# control_board.net
KiCad netlist of a schematic drawn in EAGLE
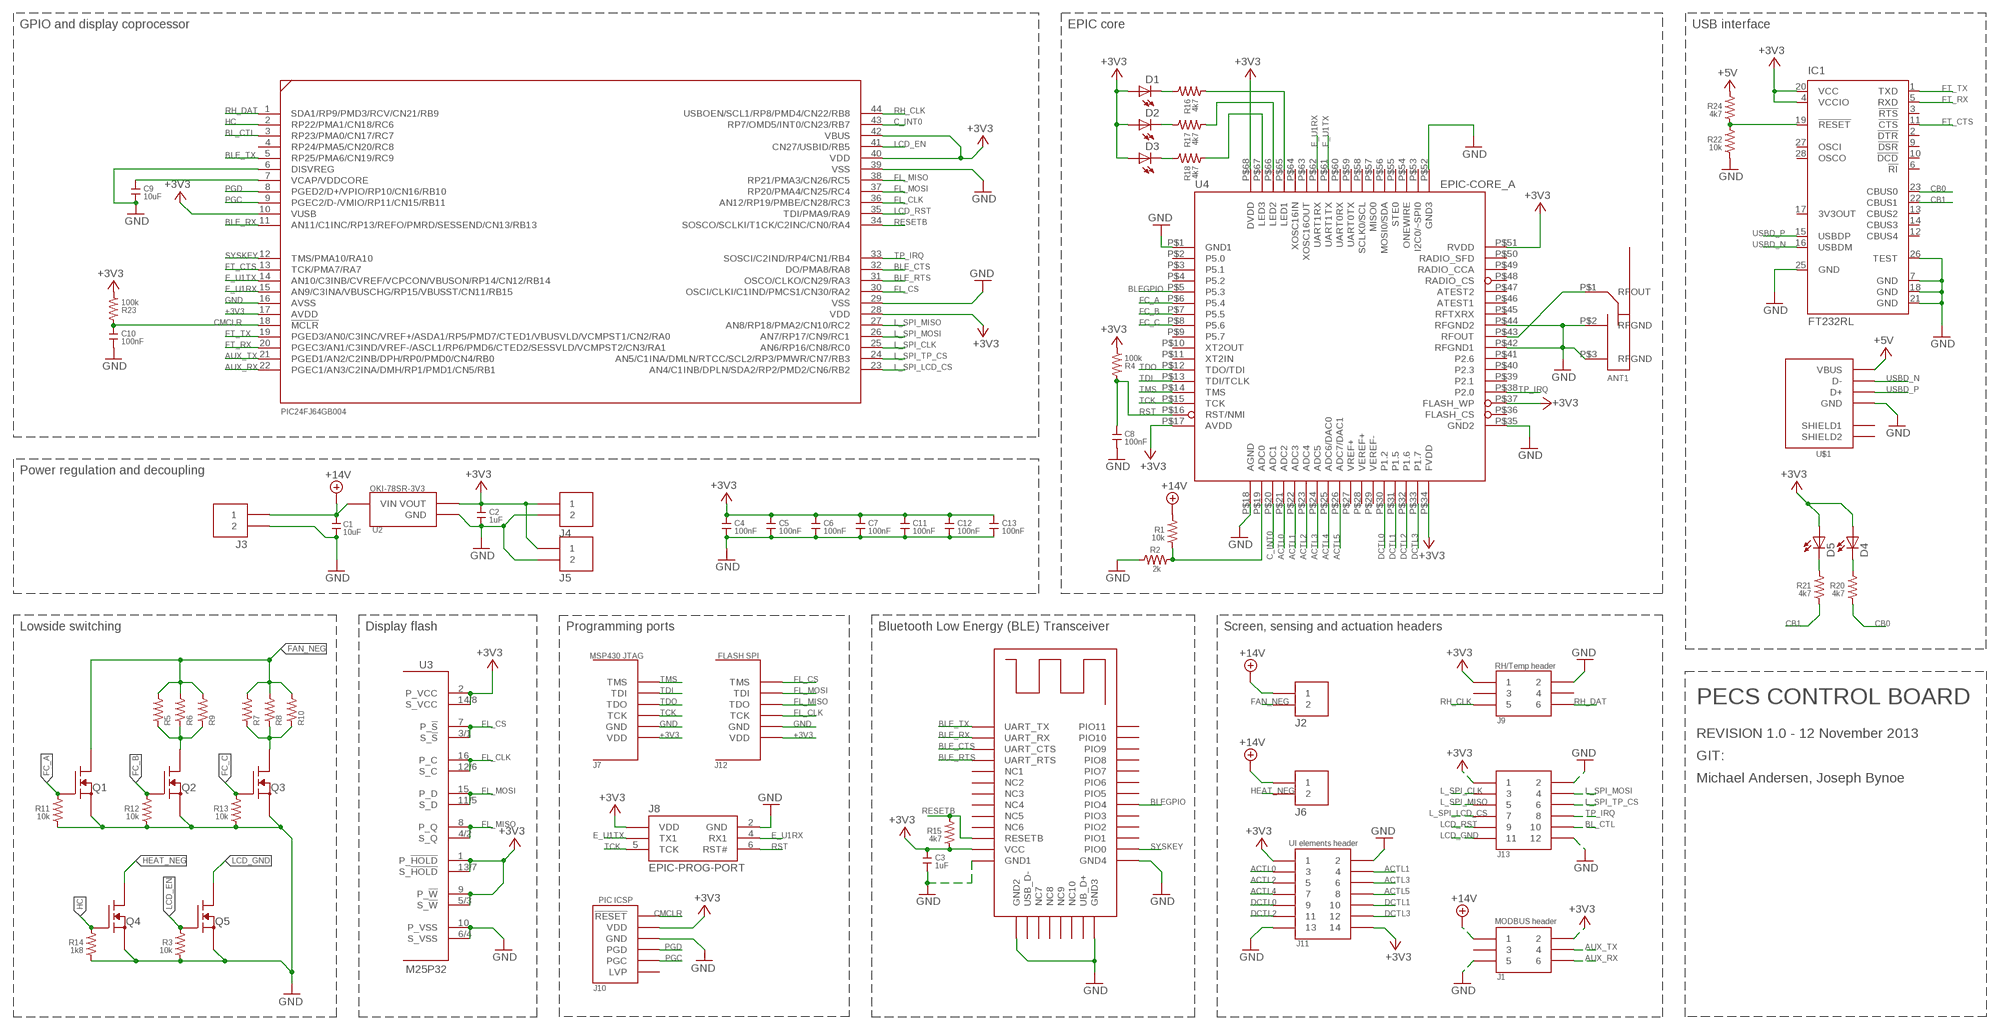
[diagram p0: schematic, sheet 1]

(export (version "E")
  (design (tool "Eeschema 10.0.6"))
  (components
    (comp (ref "ANT1")
      (value "PIFA-2.4GHZ")
      (footprint "eagle-import:PIFA-2.4GHZ")
      (libsource (lib "eagle-import") (part "PIFA-2.4GHZ"))
    )
    (comp (ref "BLE1")
      (value "HM10_BLE")
      (footprint "eagle-import:HM10")
      (libsource (lib "eagle-import") (part "HM10_BLE"))
    )
    (comp (ref "C1")
      (value "10uF")
      (footprint "eagle-import:0805")
      (libsource (lib "eagle-import") (part "0805_CAPACITOR"))
    )
    (comp (ref "C2")
      (value "1uF")
      (footprint "eagle-import:0805")
      (libsource (lib "eagle-import") (part "0805_CAPACITOR"))
    )
    (comp (ref "C3")
      (value "1uF")
      (footprint "eagle-import:0805")
      (libsource (lib "eagle-import") (part "0805_CAPACITOR"))
    )
    (comp (ref "C4")
      (value "100nF")
      (footprint "eagle-import:0805")
      (libsource (lib "eagle-import") (part "0805_CAPACITOR"))
    )
    (comp (ref "C5")
      (value "100nF")
      (footprint "eagle-import:0805")
      (libsource (lib "eagle-import") (part "0805_CAPACITOR"))
    )
    (comp (ref "C6")
      (value "100nF")
      (footprint "eagle-import:0805")
      (libsource (lib "eagle-import") (part "0805_CAPACITOR"))
    )
    (comp (ref "C7")
      (value "100nF")
      (footprint "eagle-import:0805")
      (libsource (lib "eagle-import") (part "0805_CAPACITOR"))
    )
    (comp (ref "C8")
      (value "100nF")
      (footprint "eagle-import:0805")
      (libsource (lib "eagle-import") (part "0805_CAPACITOR"))
    )
    (comp (ref "C9")
      (value "10uF")
      (footprint "eagle-import:0805")
      (libsource (lib "eagle-import") (part "0805_CAPACITOR"))
    )
    (comp (ref "C10")
      (value "100nF")
      (footprint "eagle-import:0805")
      (libsource (lib "eagle-import") (part "0805_CAPACITOR"))
    )
    (comp (ref "C11")
      (value "100nF")
      (footprint "eagle-import:0805")
      (libsource (lib "eagle-import") (part "0805_CAPACITOR"))
    )
    (comp (ref "C12")
      (value "100nF")
      (footprint "eagle-import:0805")
      (libsource (lib "eagle-import") (part "0805_CAPACITOR"))
    )
    (comp (ref "C13")
      (value "100nF")
      (footprint "eagle-import:0805")
      (libsource (lib "eagle-import") (part "0805_CAPACITOR"))
    )
    (comp (ref "D1")
      (value "LED1206")
      (footprint "eagle-import:LED-1206")
      (libsource (lib "eagle-import") (part "LED1206"))
    )
    (comp (ref "D2")
      (value "LED1206")
      (footprint "eagle-import:LED-1206")
      (libsource (lib "eagle-import") (part "LED1206"))
    )
    (comp (ref "D3")
      (value "LED1206")
      (footprint "eagle-import:LED-1206")
      (libsource (lib "eagle-import") (part "LED1206"))
    )
    (comp (ref "D4")
      (value "LED1206")
      (footprint "eagle-import:LED-1206")
      (libsource (lib "eagle-import") (part "LED1206"))
    )
    (comp (ref "D5")
      (value "LED1206")
      (footprint "eagle-import:LED-1206")
      (libsource (lib "eagle-import") (part "LED1206"))
    )
    (comp (ref "IC1")
      (value "FT232RL")
      (footprint "eagle-import:SSOP28")
      (libsource (lib "eagle-import") (part "FT232RL"))
    )
    (comp (ref "J1")
      (value "HD.1-6")
      (footprint "eagle-import:HD.1-6")
      (libsource (lib "eagle-import") (part "HD.1-6"))
    )
    (comp (ref "J2")
      (value "H.1-2")
      (footprint "eagle-import:H.1-2")
      (libsource (lib "eagle-import") (part "H.1-2"))
    )
    (comp (ref "J3")
      (value "H.1-2")
      (footprint "eagle-import:H.1-2")
      (libsource (lib "eagle-import") (part "H.1-2"))
    )
    (comp (ref "J4")
      (value "H.1-2")
      (footprint "eagle-import:H.1-2")
      (libsource (lib "eagle-import") (part "H.1-2"))
    )
    (comp (ref "J5")
      (value "H.1-2")
      (footprint "eagle-import:H.1-2")
      (libsource (lib "eagle-import") (part "H.1-2"))
    )
    (comp (ref "J6")
      (value "H.1-2")
      (footprint "eagle-import:H.1-2")
      (libsource (lib "eagle-import") (part "H.1-2"))
    )
    (comp (ref "J7")
      (value "JTAG")
      (footprint "eagle-import:JTAG")
      (libsource (lib "eagle-import") (part "JTAG"))
    )
    (comp (ref "J8")
      (value "EPIC-PROG-PORT")
      (footprint "eagle-import:HEADER2X3X2MM")
      (libsource (lib "eagle-import") (part "EPIC-PROG-PORT"))
    )
    (comp (ref "J9")
      (value "HD.1-6")
      (footprint "eagle-import:HD.1-6")
      (libsource (lib "eagle-import") (part "HD.1-6"))
    )
    (comp (ref "J10")
      (value "ICSP_HDR")
      (footprint "eagle-import:H.1-6")
      (libsource (lib "eagle-import") (part "ICSP_HDR"))
    )
    (comp (ref "J11")
      (value "HD.1-14")
      (footprint "eagle-import:HD.1-16")
      (libsource (lib "eagle-import") (part "HD.1-14"))
    )
    (comp (ref "J12")
      (value "JTAG")
      (footprint "eagle-import:JTAG")
      (libsource (lib "eagle-import") (part "JTAG"))
    )
    (comp (ref "J13")
      (value "HD.1-12")
      (footprint "eagle-import:HD.1-12")
      (libsource (lib "eagle-import") (part "HD.1-12"))
    )
    (comp (ref "Q1")
      (value "NFET_DPAK")
      (footprint "eagle-import:DPAK")
      (libsource (lib "eagle-import") (part "NFET_DPAK"))
    )
    (comp (ref "Q2")
      (value "NFET_DPAK")
      (footprint "eagle-import:DPAK")
      (libsource (lib "eagle-import") (part "NFET_DPAK"))
    )
    (comp (ref "Q3")
      (value "NFET_DPAK")
      (footprint "eagle-import:DPAK")
      (libsource (lib "eagle-import") (part "NFET_DPAK"))
    )
    (comp (ref "Q4")
      (value "NFET_DPAK")
      (footprint "eagle-import:DPAK")
      (libsource (lib "eagle-import") (part "NFET_DPAK"))
    )
    (comp (ref "Q5")
      (value "NFET_DPAK")
      (footprint "eagle-import:DPAK")
      (libsource (lib "eagle-import") (part "NFET_DPAK"))
    )
    (comp (ref "R1")
      (value "10k")
      (footprint "eagle-import:0805")
      (libsource (lib "eagle-import") (part "0805_RESISTOR"))
    )
    (comp (ref "R2")
      (value "2k")
      (footprint "eagle-import:0805")
      (libsource (lib "eagle-import") (part "0805_RESISTOR"))
    )
    (comp (ref "R3")
      (value "10k")
      (footprint "eagle-import:0805")
      (libsource (lib "eagle-import") (part "0805_RESISTOR"))
    )
    (comp (ref "R4")
      (value "100k")
      (footprint "eagle-import:0805")
      (libsource (lib "eagle-import") (part "0805_RESISTOR"))
    )
    (comp (ref "R5")
      (value "1206_RESISTOR")
      (footprint "eagle-import:1206")
      (libsource (lib "eagle-import") (part "1206_RESISTOR"))
    )
    (comp (ref "R6")
      (value "1206_RESISTOR")
      (footprint "eagle-import:1206")
      (libsource (lib "eagle-import") (part "1206_RESISTOR"))
    )
    (comp (ref "R7")
      (value "1206_RESISTOR")
      (footprint "eagle-import:1206")
      (libsource (lib "eagle-import") (part "1206_RESISTOR"))
    )
    (comp (ref "R8")
      (value "1206_RESISTOR")
      (footprint "eagle-import:1206")
      (libsource (lib "eagle-import") (part "1206_RESISTOR"))
    )
    (comp (ref "R9")
      (value "1206_RESISTOR")
      (footprint "eagle-import:1206")
      (libsource (lib "eagle-import") (part "1206_RESISTOR"))
    )
    (comp (ref "R10")
      (value "1206_RESISTOR")
      (footprint "eagle-import:1206")
      (libsource (lib "eagle-import") (part "1206_RESISTOR"))
    )
    (comp (ref "R11")
      (value "10k")
      (footprint "eagle-import:0805")
      (libsource (lib "eagle-import") (part "0805_RESISTOR"))
    )
    (comp (ref "R12")
      (value "10k")
      (footprint "eagle-import:0805")
      (libsource (lib "eagle-import") (part "0805_RESISTOR"))
    )
    (comp (ref "R13")
      (value "10k")
      (footprint "eagle-import:0805")
      (libsource (lib "eagle-import") (part "0805_RESISTOR"))
    )
    (comp (ref "R14")
      (value "1k8")
      (footprint "eagle-import:0805")
      (libsource (lib "eagle-import") (part "0805_RESISTOR"))
    )
    (comp (ref "R15")
      (value "4k7")
      (footprint "eagle-import:0805")
      (libsource (lib "eagle-import") (part "0805_RESISTOR"))
    )
    (comp (ref "R16")
      (value "4k7")
      (footprint "eagle-import:0805")
      (libsource (lib "eagle-import") (part "0805_RESISTOR"))
    )
    (comp (ref "R17")
      (value "4k7")
      (footprint "eagle-import:0805")
      (libsource (lib "eagle-import") (part "0805_RESISTOR"))
    )
    (comp (ref "R18")
      (value "4k7")
      (footprint "eagle-import:0805")
      (libsource (lib "eagle-import") (part "0805_RESISTOR"))
    )
    (comp (ref "R20")
      (value "4k7")
      (footprint "eagle-import:0805")
      (libsource (lib "eagle-import") (part "0805_RESISTOR"))
    )
    (comp (ref "R21")
      (value "4k7")
      (footprint "eagle-import:0805")
      (libsource (lib "eagle-import") (part "0805_RESISTOR"))
    )
    (comp (ref "R22")
      (value "10k")
      (footprint "eagle-import:0805")
      (libsource (lib "eagle-import") (part "0805_RESISTOR"))
    )
    (comp (ref "R23")
      (value "100k")
      (footprint "eagle-import:0805")
      (libsource (lib "eagle-import") (part "0805_RESISTOR"))
    )
    (comp (ref "R24")
      (value "4k7")
      (footprint "eagle-import:0805")
      (libsource (lib "eagle-import") (part "0805_RESISTOR"))
    )
    (comp (ref "U$1")
      (value "USB_B")
      (footprint "eagle-import:USB_MOLEX_7041")
      (libsource (lib "eagle-import") (part "USB_B"))
    )
    (comp (ref "U1")
      (value "PIC24FJ32GB004")
      (footprint "eagle-import:TQFP44")
      (libsource (lib "eagle-import") (part "PIC24FJ32GB004"))
    )
    (comp (ref "U2")
      (value "OKI-78SR_3V3_SMPS")
      (footprint "eagle-import:SMPS_MODULE")
      (libsource (lib "eagle-import") (part "OKI-78SR_3V3_SMPS"))
    )
    (comp (ref "U3")
      (value "NUMONYX_FLASH")
      (footprint "eagle-import:NUMONYX_FLASH")
      (libsource (lib "eagle-import") (part "NUMONYX_FLASH"))
    )
    (comp (ref "U4")
      (value "EPIC-CORE_A")
      (footprint "eagle-import:EPIC-LCC68")
      (libsource (lib "eagle-import") (part "EPIC-CORE_A"))
    )
  )
  (nets
    (net (code "1") (name "+3V3") (class "Default")
      (node (ref "BLE1") (pin "P$12") (pinfunction "VCC_P$12") (pintype "power_in"))
      (node (ref "C11") (pin "2") (pinfunction "P$2_2") (pintype "passive"))
      (node (ref "C12") (pin "2") (pinfunction "P$2_2") (pintype "passive"))
      (node (ref "C13") (pin "2") (pinfunction "P$2_2") (pintype "passive"))
      (node (ref "C2") (pin "2") (pinfunction "P$2_2") (pintype "passive"))
      (node (ref "C3") (pin "2") (pinfunction "P$2_2") (pintype "passive"))
      (node (ref "C4") (pin "2") (pinfunction "P$2_2") (pintype "passive"))
      (node (ref "C5") (pin "2") (pinfunction "P$2_2") (pintype "passive"))
      (node (ref "C6") (pin "2") (pinfunction "P$2_2") (pintype "passive"))
      (node (ref "C7") (pin "2") (pinfunction "P$2_2") (pintype "passive"))
      (node (ref "D1") (pin "A") (pinfunction "A_A") (pintype "passive"))
      (node (ref "D2") (pin "A") (pinfunction "A_A") (pintype "passive"))
      (node (ref "D3") (pin "A") (pinfunction "A_A") (pintype "passive"))
      (node (ref "D4") (pin "A") (pinfunction "A_A") (pintype "passive"))
      (node (ref "D5") (pin "A") (pinfunction "A_A") (pintype "passive"))
      (node (ref "IC1") (pin "20") (pinfunction "VCC_20") (pintype "power_in"))
      (node (ref "IC1") (pin "4") (pinfunction "VCCIO_4") (pintype "power_in"))
      (node (ref "J1") (pin "P2") (pinfunction "2_P2") (pintype "bidirectional"))
      (node (ref "J10") (pin "P2") (pinfunction "VDD_P2") (pintype "bidirectional"))
      (node (ref "J11") (pin "P1") (pinfunction "1_P1") (pintype "bidirectional"))
      (node (ref "J11") (pin "P14") (pinfunction "14_P14") (pintype "bidirectional"))
      (node (ref "J12") (pin "VDD") (pinfunction "VDD_VDD") (pintype "bidirectional"))
      (node (ref "J13") (pin "P1") (pinfunction "1_P1") (pintype "bidirectional"))
      (node (ref "J4") (pin "P1") (pinfunction "1_P1") (pintype "bidirectional"))
      (node (ref "J5") (pin "P1") (pinfunction "1_P1") (pintype "bidirectional"))
      (node (ref "J7") (pin "VDD") (pinfunction "VDD_VDD") (pintype "bidirectional"))
      (node (ref "J8") (pin "1") (pinfunction "VDD_1") (pintype "bidirectional"))
      (node (ref "J9") (pin "P1") (pinfunction "1_P1") (pintype "bidirectional"))
      (node (ref "R15") (pin "1") (pinfunction "P$1_1") (pintype "passive"))
      (node (ref "R23") (pin "1") (pinfunction "P$1_1") (pintype "passive"))
      (node (ref "R4") (pin "1") (pinfunction "P$1_1") (pintype "passive"))
      (node (ref "U1") (pin "10") (pinfunction "VUSB_10") (pintype "bidirectional"))
      (node (ref "U1") (pin "17") (pinfunction "AVDD_17") (pintype "bidirectional"))
      (node (ref "U1") (pin "28") (pinfunction "VDD_28") (pintype "bidirectional"))
      (node (ref "U1") (pin "40") (pinfunction "VDD_40") (pintype "bidirectional"))
      (node (ref "U1") (pin "42") (pinfunction "VBUS_42") (pintype "bidirectional"))
      (node (ref "U2") (pin "VOUT") (pinfunction "VOUT_VOUT") (pintype "power_in"))
      (node (ref "U3") (pin "1") (pinfunction "P_~{HOLD}_1") (pintype "bidirectional"))
      (node (ref "U3") (pin "13/7") (pinfunction "S_~{HOLD}_13/7") (pintype "bidirectional"))
      (node (ref "U3") (pin "14/8") (pinfunction "S_VCC_14/8") (pintype "power_in"))
      (node (ref "U3") (pin "2") (pinfunction "P_VCC_2") (pintype "power_in"))
      (node (ref "U3") (pin "5/3") (pinfunction "S_~{W}_5/3") (pintype "bidirectional"))
      (node (ref "U3") (pin "9") (pinfunction "P_~{W}_9") (pintype "bidirectional"))
      (node (ref "U4") (pin "P$17") (pinfunction "AVDD_P$17") (pintype "bidirectional"))
      (node (ref "U4") (pin "P$34") (pinfunction "FVDD_P$34") (pintype "bidirectional"))
      (node (ref "U4") (pin "P$37") (pinfunction "FLASH_WP_P$37") (pintype "bidirectional"))
      (node (ref "U4") (pin "P$51") (pinfunction "RVDD_P$51") (pintype "bidirectional"))
      (node (ref "U4") (pin "P$68") (pinfunction "DVDD_P$68") (pintype "bidirectional"))
    )
    (net (code "2") (name "+5V") (class "Default")
      (node (ref "R24") (pin "2") (pinfunction "P$2_2") (pintype "passive"))
      (node (ref "U$1") (pin "1_VBUS") (pinfunction "VBUS_1_VBUS") (pintype "bidirectional"))
    )
    (net (code "3") (name "+14V") (class "Default")
      (node (ref "C1") (pin "2") (pinfunction "P$2_2") (pintype "passive"))
      (node (ref "J1") (pin "P1") (pinfunction "1_P1") (pintype "bidirectional"))
      (node (ref "J2") (pin "P1") (pinfunction "1_P1") (pintype "bidirectional"))
      (node (ref "J3") (pin "P1") (pinfunction "1_P1") (pintype "bidirectional"))
      (node (ref "J6") (pin "P1") (pinfunction "1_P1") (pintype "bidirectional"))
      (node (ref "R1") (pin "2") (pinfunction "P$2_2") (pintype "passive"))
      (node (ref "U2") (pin "VIN") (pinfunction "VIN_VIN") (pintype "power_in"))
    )
    (net (code "4") (name "/ACTL0") (class "Default")
      (node (ref "J11") (pin "P3") (pinfunction "3_P3") (pintype "bidirectional"))
      (node (ref "U4") (pin "P$21") (pinfunction "ADC2_P$21") (pintype "bidirectional"))
    )
    (net (code "5") (name "/ACTL1") (class "Default")
      (node (ref "J11") (pin "P4") (pinfunction "4_P4") (pintype "bidirectional"))
      (node (ref "U4") (pin "P$22") (pinfunction "ADC3_P$22") (pintype "bidirectional"))
    )
    (net (code "6") (name "/ACTL2") (class "Default")
      (node (ref "J11") (pin "P5") (pinfunction "5_P5") (pintype "bidirectional"))
      (node (ref "U4") (pin "P$23") (pinfunction "ADC4_P$23") (pintype "bidirectional"))
    )
    (net (code "7") (name "/ACTL3") (class "Default")
      (node (ref "J11") (pin "P6") (pinfunction "6_P6") (pintype "bidirectional"))
      (node (ref "U4") (pin "P$24") (pinfunction "ADC5_P$24") (pintype "bidirectional"))
    )
    (net (code "8") (name "/ACTL4") (class "Default")
      (node (ref "J11") (pin "P7") (pinfunction "7_P7") (pintype "bidirectional"))
      (node (ref "U4") (pin "P$25") (pinfunction "ADC6/DAC0_P$25") (pintype "bidirectional"))
    )
    (net (code "9") (name "/ACTL5") (class "Default")
      (node (ref "J11") (pin "P8") (pinfunction "8_P8") (pintype "bidirectional"))
      (node (ref "U4") (pin "P$26") (pinfunction "ADC7/DAC1_P$26") (pintype "bidirectional"))
    )
    (net (code "10") (name "/AUX_RX") (class "Default")
      (node (ref "J1") (pin "P6") (pinfunction "6_P6") (pintype "bidirectional"))
      (node (ref "U1") (pin "22") (pinfunction "PGEC1/AN3/C2INA/DMH/RP1/PMD1/CN5/RB1_22") (pintype "bidirectional"))
    )
    (net (code "11") (name "/AUX_TX") (class "Default")
      (node (ref "J1") (pin "P4") (pinfunction "4_P4") (pintype "bidirectional"))
      (node (ref "U1") (pin "21") (pinfunction "PGED1/AN2/C2INB/DPH/RP0/PMD0/CN4/RB0_21") (pintype "bidirectional"))
    )
    (net (code "12") (name "/BLEGPIO") (class "Default")
      (node (ref "BLE1") (pin "P$27") (pinfunction "PIO4_P$27") (pintype "bidirectional"))
      (node (ref "U4") (pin "P$5") (pinfunction "P5.3_P$5") (pintype "bidirectional"))
    )
    (net (code "13") (name "/BLE_CTS") (class "Default")
      (node (ref "BLE1") (pin "P$3") (pinfunction "UART_CTS_P$3") (pintype "bidirectional"))
      (node (ref "U1") (pin "32") (pinfunction "DO/PMA8/RA8_32") (pintype "bidirectional"))
    )
    (net (code "14") (name "/BLE_RTS") (class "Default")
      (node (ref "BLE1") (pin "P$4") (pinfunction "UART_RTS_P$4") (pintype "bidirectional"))
      (node (ref "U1") (pin "31") (pinfunction "OSCO/CLKO/CN29/RA3_31") (pintype "bidirectional"))
    )
    (net (code "15") (name "/BLE_RX") (class "Default")
      (node (ref "BLE1") (pin "P$2") (pinfunction "UART_RX_P$2") (pintype "bidirectional"))
      (node (ref "U1") (pin "11") (pinfunction "AN11/C1INC/RP13/REFO/PMRD/SESSEND/CN13/RB13_11") (pintype "bidirectional"))
    )
    (net (code "16") (name "/BLE_TX") (class "Default")
      (node (ref "BLE1") (pin "P$1") (pinfunction "UART_TX_P$1") (pintype "bidirectional"))
      (node (ref "U1") (pin "5") (pinfunction "RP25/PMA6/CN19/RC9_5") (pintype "bidirectional"))
    )
    (net (code "17") (name "/BL_CTL") (class "Default")
      (node (ref "J13") (pin "P10") (pinfunction "10_P10") (pintype "bidirectional"))
      (node (ref "U1") (pin "3") (pinfunction "RP23/PMA0/CN17/RC7_3") (pintype "bidirectional"))
    )
    (net (code "18") (name "/CB0") (class "Default")
      (node (ref "IC1") (pin "23") (pinfunction "CBUS0_23") (pintype "bidirectional"))
      (node (ref "R20") (pin "1") (pinfunction "P$1_1") (pintype "passive"))
    )
    (net (code "19") (name "/CB1") (class "Default")
      (node (ref "IC1") (pin "22") (pinfunction "CBUS1_22") (pintype "bidirectional"))
      (node (ref "R21") (pin "1") (pinfunction "P$1_1") (pintype "passive"))
    )
    (net (code "20") (name "/CMCLR") (class "Default")
      (node (ref "C10") (pin "2") (pinfunction "P$2_2") (pintype "passive"))
      (node (ref "J10") (pin "P1") (pinfunction "~{RESET}_P1") (pintype "bidirectional"))
      (node (ref "R23") (pin "2") (pinfunction "P$2_2") (pintype "passive"))
      (node (ref "U1") (pin "18") (pinfunction "~{MCLR}_18") (pintype "bidirectional"))
    )
    (net (code "21") (name "/C_INT0") (class "Default")
      (node (ref "U1") (pin "43") (pinfunction "RP7/OMD5/INT0/CN23/RB7_43") (pintype "bidirectional"))
      (node (ref "U4") (pin "P$20") (pinfunction "ADC1_P$20") (pintype "bidirectional"))
    )
    (net (code "22") (name "/DCTL0") (class "Default")
      (node (ref "J11") (pin "P9") (pinfunction "9_P9") (pintype "bidirectional"))
      (node (ref "U4") (pin "P$30") (pinfunction "P1.2_P$30") (pintype "bidirectional"))
    )
    (net (code "23") (name "/DCTL1") (class "Default")
      (node (ref "J11") (pin "P10") (pinfunction "10_P10") (pintype "bidirectional"))
      (node (ref "U4") (pin "P$31") (pinfunction "P1.5_P$31") (pintype "bidirectional"))
    )
    (net (code "24") (name "/DCTL2") (class "Default")
      (node (ref "J11") (pin "P11") (pinfunction "11_P11") (pintype "bidirectional"))
      (node (ref "U4") (pin "P$32") (pinfunction "P1.6_P$32") (pintype "bidirectional"))
    )
    (net (code "25") (name "/DCTL3") (class "Default")
      (node (ref "J11") (pin "P12") (pinfunction "12_P12") (pintype "bidirectional"))
      (node (ref "U4") (pin "P$33") (pinfunction "P1.7_P$33") (pintype "bidirectional"))
    )
    (net (code "26") (name "/E_U1RX") (class "Default")
      (node (ref "J8") (pin "4") (pinfunction "RX1_4") (pintype "bidirectional"))
      (node (ref "U1") (pin "15") (pinfunction "AN9/C3INA/VBUSCHG/RP15/VBUSST/CN11/RB15_15") (pintype "bidirectional"))
      (node (ref "U4") (pin "P$62") (pinfunction "UART1RX_P$62") (pintype "bidirectional"))
    )
    (net (code "27") (name "/E_U1TX") (class "Default")
      (node (ref "J8") (pin "3") (pinfunction "TX1_3") (pintype "bidirectional"))
      (node (ref "U1") (pin "14") (pinfunction "AN10/C3INB/CVREF/VCPCON/VBUSON/RP14/CN12/RB14_14") (pintype "bidirectional"))
      (node (ref "U4") (pin "P$61") (pinfunction "UART1TX_P$61") (pintype "bidirectional"))
    )
    (net (code "28") (name "/FL_CLK") (class "Default")
      (node (ref "J12") (pin "TCK") (pinfunction "TCK_TCK") (pintype "bidirectional"))
      (node (ref "U1") (pin "36") (pinfunction "AN12/RP19/PMBE/CN28/RC3_36") (pintype "bidirectional"))
      (node (ref "U3") (pin "12/6") (pinfunction "S_C_12/6") (pintype "bidirectional"))
      (node (ref "U3") (pin "16") (pinfunction "P_C_16") (pintype "bidirectional"))
    )
    (net (code "29") (name "/FL_CS") (class "Default")
      (node (ref "J12") (pin "TMS") (pinfunction "TMS_TMS") (pintype "bidirectional"))
      (node (ref "U1") (pin "30") (pinfunction "OSCI/CLKI/C1IND/PMCS1/CN30/RA2_30") (pintype "bidirectional"))
      (node (ref "U3") (pin "3/1") (pinfunction "S_~{S}_3/1") (pintype "bidirectional"))
      (node (ref "U3") (pin "7") (pinfunction "P_~{S}_7") (pintype "bidirectional"))
    )
    (net (code "30") (name "/FL_MISO") (class "Default")
      (node (ref "J12") (pin "TDO") (pinfunction "TDO_TDO") (pintype "bidirectional"))
      (node (ref "U1") (pin "38") (pinfunction "RP21/PMA3/CN26/RC5_38") (pintype "bidirectional"))
      (node (ref "U3") (pin "4/2") (pinfunction "S_Q_4/2") (pintype "bidirectional"))
      (node (ref "U3") (pin "8") (pinfunction "P_Q_8") (pintype "bidirectional"))
    )
    (net (code "31") (name "/FL_MOSI") (class "Default")
      (node (ref "J12") (pin "TDI") (pinfunction "TDI_TDI") (pintype "bidirectional"))
      (node (ref "U1") (pin "37") (pinfunction "RP20/PMA4/CN25/RC4_37") (pintype "bidirectional"))
      (node (ref "U3") (pin "11/5") (pinfunction "S_D_11/5") (pintype "bidirectional"))
      (node (ref "U3") (pin "15") (pinfunction "P_D_15") (pintype "bidirectional"))
    )
    (net (code "32") (name "/FT_CTS") (class "Default")
      (node (ref "IC1") (pin "11") (pinfunction "~{CTS}_11") (pintype "input"))
      (node (ref "U1") (pin "13") (pinfunction "TCK/PMA7/RA7_13") (pintype "bidirectional"))
    )
    (net (code "33") (name "/FT_RX") (class "Default")
      (node (ref "IC1") (pin "5") (pinfunction "RXD_5") (pintype "input"))
      (node (ref "U1") (pin "20") (pinfunction "PGEC3/AN1/C3IND/VREF-/ASCL1/RP6/PMD6/CTED2/SESSVLD/VCMPST2/CN3/RA1_20") (pintype "bidirectional"))
    )
    (net (code "34") (name "/FT_TX") (class "Default")
      (node (ref "IC1") (pin "1") (pinfunction "TXD_1") (pintype "output"))
      (node (ref "U1") (pin "19") (pinfunction "PGED3/AN0/C3INC/VREF+/ASDA1/RP5/PMD7/CTED1/VBUSVLD/VCMPST1/CN2/RA0_19") (pintype "bidirectional"))
    )
    (net (code "35") (name "/LCD_RST") (class "Default")
      (node (ref "J13") (pin "P9") (pinfunction "9_P9") (pintype "bidirectional"))
      (node (ref "U1") (pin "35") (pinfunction "TDI/PMA9/RA9_35") (pintype "bidirectional"))
    )
    (net (code "36") (name "/L_SPI_CLK") (class "Default")
      (node (ref "J13") (pin "P3") (pinfunction "3_P3") (pintype "bidirectional"))
      (node (ref "U1") (pin "25") (pinfunction "AN6/RP16/CN8/RC0_25") (pintype "bidirectional"))
    )
    (net (code "37") (name "/L_SPI_LCD_CS") (class "Default")
      (node (ref "J13") (pin "P7") (pinfunction "7_P7") (pintype "bidirectional"))
      (node (ref "U1") (pin "23") (pinfunction "AN4/C1INB/DPLN/SDA2/RP2/PMD2/CN6/RB2_23") (pintype "bidirectional"))
    )
    (net (code "38") (name "/L_SPI_MISO") (class "Default")
      (node (ref "J13") (pin "P5") (pinfunction "5_P5") (pintype "bidirectional"))
      (node (ref "U1") (pin "27") (pinfunction "AN8/RP18/PMA2/CN10/RC2_27") (pintype "bidirectional"))
    )
    (net (code "39") (name "/L_SPI_MOSI") (class "Default")
      (node (ref "J13") (pin "P4") (pinfunction "4_P4") (pintype "bidirectional"))
      (node (ref "U1") (pin "26") (pinfunction "AN7/RP17/CN9/RC1_26") (pintype "bidirectional"))
    )
    (net (code "40") (name "/L_SPI_TP_CS") (class "Default")
      (node (ref "J13") (pin "P6") (pinfunction "6_P6") (pintype "bidirectional"))
      (node (ref "U1") (pin "24") (pinfunction "AN5/C1INA/DMLN/RTCC/SCL2/RP3/PMWR/CN7/RB3_24") (pintype "bidirectional"))
    )
    (net (code "41") (name "/PGC") (class "Default")
      (node (ref "J10") (pin "P5") (pinfunction "PGC_P5") (pintype "bidirectional"))
      (node (ref "U1") (pin "9") (pinfunction "PGEC2/D-/VMIO/RP11/CN15/RB11_9") (pintype "bidirectional"))
    )
    (net (code "42") (name "/PGD") (class "Default")
      (node (ref "J10") (pin "P4") (pinfunction "PGD_P4") (pintype "bidirectional"))
      (node (ref "U1") (pin "8") (pinfunction "PGED2/D+/VPIO/RP10/CN16/RB10_8") (pintype "bidirectional"))
    )
    (net (code "43") (name "/RESETB") (class "Default")
      (node (ref "BLE1") (pin "P$11") (pinfunction "RESETB_P$11") (pintype "input"))
      (node (ref "R15") (pin "2") (pinfunction "P$2_2") (pintype "passive"))
      (node (ref "U1") (pin "34") (pinfunction "SOSCO/SCLKI/T1CK/C2INC/CN0/RA4_34") (pintype "bidirectional"))
    )
    (net (code "44") (name "/RH_CLK") (class "Default")
      (node (ref "J9") (pin "P5") (pinfunction "5_P5") (pintype "bidirectional"))
      (node (ref "U1") (pin "44") (pinfunction "USBOEN/SCL1/RP8/PMD4/CN22/RB8_44") (pintype "bidirectional"))
    )
    (net (code "45") (name "/RH_DAT") (class "Default")
      (node (ref "J9") (pin "P6") (pinfunction "6_P6") (pintype "bidirectional"))
      (node (ref "U1") (pin "1") (pinfunction "SDA1/RP9/PMD3/RCV/CN21/RB9_1") (pintype "bidirectional"))
    )
    (net (code "46") (name "/RST") (class "Default")
      (node (ref "C8") (pin "2") (pinfunction "P$2_2") (pintype "passive"))
      (node (ref "J8") (pin "6") (pinfunction "RST#_6") (pintype "bidirectional"))
      (node (ref "R4") (pin "2") (pinfunction "P$2_2") (pintype "passive"))
      (node (ref "U4") (pin "P$16") (pinfunction "RST/NMI_P$16") (pintype "bidirectional"))
    )
    (net (code "47") (name "/SYSKEY") (class "Default")
      (node (ref "BLE1") (pin "P$23") (pinfunction "PIO0_P$23") (pintype "bidirectional"))
      (node (ref "U1") (pin "12") (pinfunction "TMS/PMA10/RA10_12") (pintype "bidirectional"))
    )
    (net (code "48") (name "/TCK") (class "Default")
      (node (ref "J7") (pin "TCK") (pinfunction "TCK_TCK") (pintype "bidirectional"))
      (node (ref "J8") (pin "5") (pinfunction "TCK_5") (pintype "bidirectional"))
      (node (ref "U4") (pin "P$15") (pinfunction "TCK_P$15") (pintype "bidirectional"))
    )
    (net (code "49") (name "/TDI") (class "Default")
      (node (ref "J7") (pin "TDI") (pinfunction "TDI_TDI") (pintype "bidirectional"))
      (node (ref "U4") (pin "P$13") (pinfunction "TDI/TCLK_P$13") (pintype "bidirectional"))
    )
    (net (code "50") (name "/TDO") (class "Default")
      (node (ref "J7") (pin "TDO") (pinfunction "TDO_TDO") (pintype "bidirectional"))
      (node (ref "U4") (pin "P$12") (pinfunction "TDO/TDI_P$12") (pintype "bidirectional"))
    )
    (net (code "51") (name "/TMS") (class "Default")
      (node (ref "J7") (pin "TMS") (pinfunction "TMS_TMS") (pintype "bidirectional"))
      (node (ref "U4") (pin "P$14") (pinfunction "TMS_P$14") (pintype "bidirectional"))
    )
    (net (code "52") (name "/TP_IRQ") (class "Default")
      (node (ref "J13") (pin "P8") (pinfunction "8_P8") (pintype "bidirectional"))
      (node (ref "U1") (pin "33") (pinfunction "SOSCI/C2IND/RP4/CN1/RB4_33") (pintype "bidirectional"))
      (node (ref "U4") (pin "P$38") (pinfunction "P2.0_P$38") (pintype "bidirectional"))
    )
    (net (code "53") (name "/USBD_N") (class "Default")
      (node (ref "IC1") (pin "16") (pinfunction "USBDM_16") (pintype "bidirectional"))
      (node (ref "U$1") (pin "2_D-") (pinfunction "D-_2_D-") (pintype "bidirectional"))
    )
    (net (code "54") (name "/USBD_P") (class "Default")
      (node (ref "IC1") (pin "15") (pinfunction "USBDP_15") (pintype "bidirectional"))
      (node (ref "U$1") (pin "3_D+") (pinfunction "D+_3_D+") (pintype "bidirectional"))
    )
    (net (code "55") (name "FAN_NEG") (class "Default")
      (node (ref "J2") (pin "P2") (pinfunction "2_P2") (pintype "bidirectional"))
      (node (ref "Q1") (pin "TAG") (pinfunction "D_TAG") (pintype "passive"))
      (node (ref "R10") (pin "2") (pinfunction "P$2_2") (pintype "passive"))
      (node (ref "R5") (pin "2") (pinfunction "P$2_2") (pintype "passive"))
      (node (ref "R6") (pin "2") (pinfunction "P$2_2") (pintype "passive"))
      (node (ref "R7") (pin "2") (pinfunction "P$2_2") (pintype "passive"))
      (node (ref "R8") (pin "2") (pinfunction "P$2_2") (pintype "passive"))
      (node (ref "R9") (pin "2") (pinfunction "P$2_2") (pintype "passive"))
    )
    (net (code "56") (name "FC_A") (class "Default")
      (node (ref "Q1") (pin "P1") (pinfunction "G_P1") (pintype "passive"))
      (node (ref "R11") (pin "2") (pinfunction "P$2_2") (pintype "passive"))
      (node (ref "U4") (pin "P$6") (pinfunction "P5.4_P$6") (pintype "bidirectional"))
    )
    (net (code "57") (name "FC_B") (class "Default")
      (node (ref "Q2") (pin "P1") (pinfunction "G_P1") (pintype "passive"))
      (node (ref "R12") (pin "2") (pinfunction "P$2_2") (pintype "passive"))
      (node (ref "U4") (pin "P$7") (pinfunction "P5.5_P$7") (pintype "bidirectional"))
    )
    (net (code "58") (name "FC_C") (class "Default")
      (node (ref "Q3") (pin "P1") (pinfunction "G_P1") (pintype "passive"))
      (node (ref "R13") (pin "2") (pinfunction "P$2_2") (pintype "passive"))
      (node (ref "U4") (pin "P$8") (pinfunction "P5.6_P$8") (pintype "bidirectional"))
    )
    (net (code "59") (name "GND") (class "Default")
      (node (ref "ANT1") (pin "P$2") (pinfunction "RFGND_P$2") (pintype "bidirectional"))
      (node (ref "ANT1") (pin "P$3") (pinfunction "RFGND_P$3") (pintype "bidirectional"))
      (node (ref "BLE1") (pin "P$13") (pinfunction "GND1_P$13") (pintype "power_in"))
      (node (ref "BLE1") (pin "P$14") (pinfunction "GND2_P$14") (pintype "power_in"))
      (node (ref "BLE1") (pin "P$21") (pinfunction "GND3_P$21") (pintype "power_in"))
      (node (ref "BLE1") (pin "P$22") (pinfunction "GND4_P$22") (pintype "power_in"))
      (node (ref "C1") (pin "1") (pinfunction "P$1_1") (pintype "passive"))
      (node (ref "C10") (pin "1") (pinfunction "P$1_1") (pintype "passive"))
      (node (ref "C11") (pin "1") (pinfunction "P$1_1") (pintype "passive"))
      (node (ref "C12") (pin "1") (pinfunction "P$1_1") (pintype "passive"))
      (node (ref "C13") (pin "1") (pinfunction "P$1_1") (pintype "passive"))
      (node (ref "C2") (pin "1") (pinfunction "P$1_1") (pintype "passive"))
      (node (ref "C3") (pin "1") (pinfunction "P$1_1") (pintype "passive"))
      (node (ref "C4") (pin "1") (pinfunction "P$1_1") (pintype "passive"))
      (node (ref "C5") (pin "1") (pinfunction "P$1_1") (pintype "passive"))
      (node (ref "C6") (pin "1") (pinfunction "P$1_1") (pintype "passive"))
      (node (ref "C7") (pin "1") (pinfunction "P$1_1") (pintype "passive"))
      (node (ref "C8") (pin "1") (pinfunction "P$1_1") (pintype "passive"))
      (node (ref "C9") (pin "1") (pinfunction "P$1_1") (pintype "passive"))
      (node (ref "IC1") (pin "18") (pinfunction "GND_18") (pintype "power_in"))
      (node (ref "IC1") (pin "21") (pinfunction "GND_21") (pintype "power_in"))
      (node (ref "IC1") (pin "25") (pinfunction "GND_25") (pintype "power_in"))
      (node (ref "IC1") (pin "26") (pinfunction "TEST_26") (pintype "input"))
      (node (ref "IC1") (pin "7") (pinfunction "GND_7") (pintype "power_in"))
      (node (ref "J1") (pin "P5") (pinfunction "5_P5") (pintype "bidirectional"))
      (node (ref "J10") (pin "P3") (pinfunction "GND_P3") (pintype "bidirectional"))
      (node (ref "J11") (pin "P13") (pinfunction "13_P13") (pintype "bidirectional"))
      (node (ref "J11") (pin "P2") (pinfunction "2_P2") (pintype "bidirectional"))
      (node (ref "J12") (pin "GND") (pinfunction "GND_GND") (pintype "bidirectional"))
      (node (ref "J13") (pin "P12") (pinfunction "12_P12") (pintype "bidirectional"))
      (node (ref "J13") (pin "P2") (pinfunction "2_P2") (pintype "bidirectional"))
      (node (ref "J3") (pin "P2") (pinfunction "2_P2") (pintype "bidirectional"))
      (node (ref "J4") (pin "P2") (pinfunction "2_P2") (pintype "bidirectional"))
      (node (ref "J5") (pin "P2") (pinfunction "2_P2") (pintype "bidirectional"))
      (node (ref "J7") (pin "GND") (pinfunction "GND_GND") (pintype "bidirectional"))
      (node (ref "J8") (pin "2") (pinfunction "GND_2") (pintype "bidirectional"))
      (node (ref "J9") (pin "P2") (pinfunction "2_P2") (pintype "bidirectional"))
      (node (ref "Q1") (pin "P3") (pinfunction "S_P3") (pintype "passive"))
      (node (ref "Q2") (pin "P3") (pinfunction "S_P3") (pintype "passive"))
      (node (ref "Q3") (pin "P3") (pinfunction "S_P3") (pintype "passive"))
      (node (ref "Q4") (pin "P3") (pinfunction "S_P3") (pintype "passive"))
      (node (ref "Q5") (pin "P3") (pinfunction "S_P3") (pintype "passive"))
      (node (ref "R11") (pin "1") (pinfunction "P$1_1") (pintype "passive"))
      (node (ref "R12") (pin "1") (pinfunction "P$1_1") (pintype "passive"))
      (node (ref "R13") (pin "1") (pinfunction "P$1_1") (pintype "passive"))
      (node (ref "R14") (pin "1") (pinfunction "P$1_1") (pintype "passive"))
      (node (ref "R2") (pin "1") (pinfunction "P$1_1") (pintype "passive"))
      (node (ref "R22") (pin "1") (pinfunction "P$1_1") (pintype "passive"))
      (node (ref "R3") (pin "1") (pinfunction "P$1_1") (pintype "passive"))
      (node (ref "U$1") (pin "4_GND") (pinfunction "GND_4_GND") (pintype "bidirectional"))
      (node (ref "U1") (pin "16") (pinfunction "AVSS_16") (pintype "bidirectional"))
      (node (ref "U1") (pin "29") (pinfunction "VSS_29") (pintype "bidirectional"))
      (node (ref "U1") (pin "39") (pinfunction "VSS_39") (pintype "bidirectional"))
      (node (ref "U1") (pin "6") (pinfunction "DISVREG_6") (pintype "bidirectional"))
      (node (ref "U2") (pin "GND") (pinfunction "GND_GND") (pintype "power_in"))
      (node (ref "U3") (pin "10") (pinfunction "P_VSS_10") (pintype "power_in"))
      (node (ref "U3") (pin "6/4") (pinfunction "S_VSS_6/4") (pintype "power_in"))
      (node (ref "U4") (pin "P$1") (pinfunction "GND1_P$1") (pintype "bidirectional"))
      (node (ref "U4") (pin "P$18") (pinfunction "AGND_P$18") (pintype "bidirectional"))
      (node (ref "U4") (pin "P$35") (pinfunction "GND2_P$35") (pintype "bidirectional"))
      (node (ref "U4") (pin "P$42") (pinfunction "RFGND1_P$42") (pintype "bidirectional"))
      (node (ref "U4") (pin "P$44") (pinfunction "RFGND2_P$44") (pintype "bidirectional"))
      (node (ref "U4") (pin "P$52") (pinfunction "GND3_P$52") (pintype "bidirectional"))
    )
    (net (code "60") (name "HC") (class "Default")
      (node (ref "Q4") (pin "P1") (pinfunction "G_P1") (pintype "passive"))
      (node (ref "R14") (pin "2") (pinfunction "P$2_2") (pintype "passive"))
      (node (ref "U1") (pin "2") (pinfunction "RP22/PMA1/CN18/RC6_2") (pintype "bidirectional"))
    )
    (net (code "61") (name "HEAT_NEG") (class "Default")
      (node (ref "J6") (pin "P2") (pinfunction "2_P2") (pintype "bidirectional"))
      (node (ref "Q4") (pin "TAG") (pinfunction "D_TAG") (pintype "passive"))
    )
    (net (code "62") (name "LCD_EN") (class "Default")
      (node (ref "Q5") (pin "P1") (pinfunction "G_P1") (pintype "passive"))
      (node (ref "R3") (pin "2") (pinfunction "P$2_2") (pintype "passive"))
      (node (ref "U1") (pin "41") (pinfunction "CN27/USBID/RB5_41") (pintype "bidirectional"))
    )
    (net (code "63") (name "LCD_GND") (class "Default")
      (node (ref "J13") (pin "P11") (pinfunction "11_P11") (pintype "bidirectional"))
      (node (ref "Q5") (pin "TAG") (pinfunction "D_TAG") (pintype "passive"))
    )
    (net (code "64") (name "Net-(ANT1-RFOUT)") (class "Default")
      (node (ref "ANT1") (pin "P$1") (pinfunction "RFOUT_P$1") (pintype "bidirectional"))
      (node (ref "U4") (pin "P$43") (pinfunction "RFOUT_P$43") (pintype "bidirectional"))
    )
    (net (code "65") (name "Net-(C9-P$2)") (class "Default")
      (node (ref "C9") (pin "2") (pinfunction "P$2_2") (pintype "passive"))
      (node (ref "U1") (pin "7") (pinfunction "VCAP/VDDCORE_7") (pintype "bidirectional"))
    )
    (net (code "66") (name "Net-(IC1-~{RESET})") (class "Default")
      (node (ref "IC1") (pin "19") (pinfunction "~{RESET}_19") (pintype "input"))
      (node (ref "R22") (pin "2") (pinfunction "P$2_2") (pintype "passive"))
      (node (ref "R24") (pin "1") (pinfunction "P$1_1") (pintype "passive"))
    )
    (net (code "67") (name "Net-(Q2-D)") (class "Default")
      (node (ref "Q2") (pin "TAG") (pinfunction "D_TAG") (pintype "passive"))
      (node (ref "R5") (pin "1") (pinfunction "P$1_1") (pintype "passive"))
      (node (ref "R6") (pin "1") (pinfunction "P$1_1") (pintype "passive"))
      (node (ref "R9") (pin "1") (pinfunction "P$1_1") (pintype "passive"))
    )
    (net (code "68") (name "Net-(Q3-D)") (class "Default")
      (node (ref "Q3") (pin "TAG") (pinfunction "D_TAG") (pintype "passive"))
      (node (ref "R10") (pin "1") (pinfunction "P$1_1") (pintype "passive"))
      (node (ref "R7") (pin "1") (pinfunction "P$1_1") (pintype "passive"))
      (node (ref "R8") (pin "1") (pinfunction "P$1_1") (pintype "passive"))
    )
    (net (code "69") (name "Net-(R1-P$1)") (class "Default")
      (node (ref "R1") (pin "1") (pinfunction "P$1_1") (pintype "passive"))
      (node (ref "R2") (pin "2") (pinfunction "P$2_2") (pintype "passive"))
      (node (ref "U4") (pin "P$19") (pinfunction "ADC0_P$19") (pintype "bidirectional"))
    )
    (net (code "70") (name "Net-(R16-P$1)") (class "Default")
      (node (ref "R16") (pin "1") (pinfunction "P$1_1") (pintype "passive"))
      (node (ref "U4") (pin "P$65") (pinfunction "LED1_P$65") (pintype "bidirectional"))
    )
    (net (code "71") (name "Net-(R16-P$2)") (class "Default")
      (node (ref "D1") (pin "C") (pinfunction "C_C") (pintype "passive"))
      (node (ref "R16") (pin "2") (pinfunction "P$2_2") (pintype "passive"))
    )
    (net (code "72") (name "Net-(R17-P$1)") (class "Default")
      (node (ref "R17") (pin "1") (pinfunction "P$1_1") (pintype "passive"))
      (node (ref "U4") (pin "P$66") (pinfunction "LED2_P$66") (pintype "bidirectional"))
    )
    (net (code "73") (name "Net-(R17-P$2)") (class "Default")
      (node (ref "D2") (pin "C") (pinfunction "C_C") (pintype "passive"))
      (node (ref "R17") (pin "2") (pinfunction "P$2_2") (pintype "passive"))
    )
    (net (code "74") (name "Net-(R18-P$1)") (class "Default")
      (node (ref "R18") (pin "1") (pinfunction "P$1_1") (pintype "passive"))
      (node (ref "U4") (pin "P$67") (pinfunction "LED3_P$67") (pintype "bidirectional"))
    )
    (net (code "75") (name "Net-(R18-P$2)") (class "Default")
      (node (ref "D3") (pin "C") (pinfunction "C_C") (pintype "passive"))
      (node (ref "R18") (pin "2") (pinfunction "P$2_2") (pintype "passive"))
    )
    (net (code "76") (name "Net-(R20-P$2)") (class "Default")
      (node (ref "D4") (pin "C") (pinfunction "C_C") (pintype "passive"))
      (node (ref "R20") (pin "2") (pinfunction "P$2_2") (pintype "passive"))
    )
    (net (code "77") (name "Net-(R21-P$2)") (class "Default")
      (node (ref "D5") (pin "C") (pinfunction "C_C") (pintype "passive"))
      (node (ref "R21") (pin "2") (pinfunction "P$2_2") (pintype "passive"))
    )
    (net (code "78") (name "unconnected-(BLE1-NC1-PadP$5)") (class "Default")
      (node (ref "BLE1") (pin "P$5") (pinfunction "NC1_P$5") (pintype "no_connect"))
    )
    (net (code "79") (name "unconnected-(BLE1-NC2-PadP$6)") (class "Default")
      (node (ref "BLE1") (pin "P$6") (pinfunction "NC2_P$6") (pintype "no_connect"))
    )
    (net (code "80") (name "unconnected-(BLE1-NC3-PadP$7)") (class "Default")
      (node (ref "BLE1") (pin "P$7") (pinfunction "NC3_P$7") (pintype "no_connect"))
    )
    (net (code "81") (name "unconnected-(BLE1-NC4-PadP$8)") (class "Default")
      (node (ref "BLE1") (pin "P$8") (pinfunction "NC4_P$8") (pintype "no_connect"))
    )
    (net (code "82") (name "unconnected-(BLE1-NC5-PadP$9)") (class "Default")
      (node (ref "BLE1") (pin "P$9") (pinfunction "NC5_P$9") (pintype "no_connect"))
    )
    (net (code "83") (name "unconnected-(BLE1-NC6-PadP$10)") (class "Default")
      (node (ref "BLE1") (pin "P$10") (pinfunction "NC6_P$10") (pintype "no_connect"))
    )
    (net (code "84") (name "unconnected-(BLE1-NC7-PadP$16)") (class "Default")
      (node (ref "BLE1") (pin "P$16") (pinfunction "NC7_P$16") (pintype "no_connect"))
    )
    (net (code "85") (name "unconnected-(BLE1-NC8-PadP$17)") (class "Default")
      (node (ref "BLE1") (pin "P$17") (pinfunction "NC8_P$17") (pintype "no_connect"))
    )
    (net (code "86") (name "unconnected-(BLE1-NC9-PadP$18)") (class "Default")
      (node (ref "BLE1") (pin "P$18") (pinfunction "NC9_P$18") (pintype "no_connect"))
    )
    (net (code "87") (name "unconnected-(BLE1-NC10-PadP$19)") (class "Default")
      (node (ref "BLE1") (pin "P$19") (pinfunction "NC10_P$19") (pintype "no_connect"))
    )
    (net (code "88") (name "unconnected-(BLE1-PIO1-PadP$24)") (class "Default")
      (node (ref "BLE1") (pin "P$24") (pinfunction "PIO1_P$24") (pintype "bidirectional"))
    )
    (net (code "89") (name "unconnected-(BLE1-PIO2-PadP$25)") (class "Default")
      (node (ref "BLE1") (pin "P$25") (pinfunction "PIO2_P$25") (pintype "bidirectional"))
    )
    (net (code "90") (name "unconnected-(BLE1-PIO3-PadP$26)") (class "Default")
      (node (ref "BLE1") (pin "P$26") (pinfunction "PIO3_P$26") (pintype "bidirectional"))
    )
    (net (code "91") (name "unconnected-(BLE1-PIO5-PadP$28)") (class "Default")
      (node (ref "BLE1") (pin "P$28") (pinfunction "PIO5_P$28") (pintype "bidirectional"))
    )
    (net (code "92") (name "unconnected-(BLE1-PIO6-PadP$29)") (class "Default")
      (node (ref "BLE1") (pin "P$29") (pinfunction "PIO6_P$29") (pintype "bidirectional"))
    )
    (net (code "93") (name "unconnected-(BLE1-PIO7-PadP$30)") (class "Default")
      (node (ref "BLE1") (pin "P$30") (pinfunction "PIO7_P$30") (pintype "bidirectional"))
    )
    (net (code "94") (name "unconnected-(BLE1-PIO8-PadP$31)") (class "Default")
      (node (ref "BLE1") (pin "P$31") (pinfunction "PIO8_P$31") (pintype "bidirectional"))
    )
    (net (code "95") (name "unconnected-(BLE1-PIO9-PadP$32)") (class "Default")
      (node (ref "BLE1") (pin "P$32") (pinfunction "PIO9_P$32") (pintype "bidirectional"))
    )
    (net (code "96") (name "unconnected-(BLE1-PIO10-PadP$33)") (class "Default")
      (node (ref "BLE1") (pin "P$33") (pinfunction "PIO10_P$33") (pintype "bidirectional"))
    )
    (net (code "97") (name "unconnected-(BLE1-PIO11-PadP$34)") (class "Default")
      (node (ref "BLE1") (pin "P$34") (pinfunction "PIO11_P$34") (pintype "bidirectional"))
    )
    (net (code "98") (name "unconnected-(BLE1-UB_D+-PadP$20)") (class "Default")
      (node (ref "BLE1") (pin "P$20") (pinfunction "UB_D+_P$20") (pintype "bidirectional"))
    )
    (net (code "99") (name "unconnected-(BLE1-USB_D--PadP$15)") (class "Default")
      (node (ref "BLE1") (pin "P$15") (pinfunction "USB_D-_P$15") (pintype "bidirectional"))
    )
    (net (code "100") (name "unconnected-(IC1-3V3OUT-Pad17)") (class "Default")
      (node (ref "IC1") (pin "17") (pinfunction "3V3OUT_17") (pintype "output"))
    )
    (net (code "101") (name "unconnected-(IC1-CBUS2-Pad13)") (class "Default")
      (node (ref "IC1") (pin "13") (pinfunction "CBUS2_13") (pintype "bidirectional"))
    )
    (net (code "102") (name "unconnected-(IC1-CBUS3-Pad14)") (class "Default")
      (node (ref "IC1") (pin "14") (pinfunction "CBUS3_14") (pintype "bidirectional"))
    )
    (net (code "103") (name "unconnected-(IC1-CBUS4-Pad12)") (class "Default")
      (node (ref "IC1") (pin "12") (pinfunction "CBUS4_12") (pintype "bidirectional"))
    )
    (net (code "104") (name "unconnected-(IC1-OSCI-Pad27)") (class "Default")
      (node (ref "IC1") (pin "27") (pinfunction "OSCI_27") (pintype "input"))
    )
    (net (code "105") (name "unconnected-(IC1-OSCO-Pad28)") (class "Default")
      (node (ref "IC1") (pin "28") (pinfunction "OSCO_28") (pintype "output"))
    )
    (net (code "106") (name "unconnected-(IC1-~{DCD}-Pad10)") (class "Default")
      (node (ref "IC1") (pin "10") (pinfunction "~{DCD}_10") (pintype "input"))
    )
    (net (code "107") (name "unconnected-(IC1-~{DSR}-Pad9)") (class "Default")
      (node (ref "IC1") (pin "9") (pinfunction "~{DSR}_9") (pintype "input"))
    )
    (net (code "108") (name "unconnected-(IC1-~{DTR}-Pad2)") (class "Default")
      (node (ref "IC1") (pin "2") (pinfunction "~{DTR}_2") (pintype "output"))
    )
    (net (code "109") (name "unconnected-(IC1-~{RI}-Pad6)") (class "Default")
      (node (ref "IC1") (pin "6") (pinfunction "~{RI}_6") (pintype "input"))
    )
    (net (code "110") (name "unconnected-(IC1-~{RTS}-Pad3)") (class "Default")
      (node (ref "IC1") (pin "3") (pinfunction "~{RTS}_3") (pintype "output"))
    )
    (net (code "111") (name "unconnected-(J1-3-PadP3)") (class "Default")
      (node (ref "J1") (pin "P3") (pinfunction "3_P3") (pintype "bidirectional"))
    )
    (net (code "112") (name "unconnected-(J9-3-PadP3)") (class "Default")
      (node (ref "J9") (pin "P3") (pinfunction "3_P3") (pintype "bidirectional"))
    )
    (net (code "113") (name "unconnected-(J9-4-PadP4)") (class "Default")
      (node (ref "J9") (pin "P4") (pinfunction "4_P4") (pintype "bidirectional"))
    )
    (net (code "114") (name "unconnected-(J10-LVP-PadP6)") (class "Default")
      (node (ref "J10") (pin "P6") (pinfunction "LVP_P6") (pintype "bidirectional"))
    )
    (net (code "115") (name "unconnected-(U$1-PadSHIELD1)") (class "Default")
      (node (ref "U$1") (pin "SHIELD1") (pinfunction "SHIELD1_SHIELD1") (pintype "bidirectional"))
    )
    (net (code "116") (name "unconnected-(U$1-PadSHIELD2)") (class "Default")
      (node (ref "U$1") (pin "SHIELD2") (pinfunction "SHIELD2_SHIELD2") (pintype "bidirectional"))
    )
    (net (code "117") (name "unconnected-(U1-RP24{slash}PMA5{slash}CN20{slash}RC8-Pad4)") (class "Default")
      (node (ref "U1") (pin "4") (pinfunction "RP24/PMA5/CN20/RC8_4") (pintype "bidirectional"))
    )
    (net (code "118") (name "unconnected-(U4-ATEST1-PadP$46)") (class "Default")
      (node (ref "U4") (pin "P$46") (pinfunction "ATEST1_P$46") (pintype "bidirectional"))
    )
    (net (code "119") (name "unconnected-(U4-ATEST2-PadP$47)") (class "Default")
      (node (ref "U4") (pin "P$47") (pinfunction "ATEST2_P$47") (pintype "bidirectional"))
    )
    (net (code "120") (name "unconnected-(U4-FLASH_CS-PadP$36)") (class "Default")
      (node (ref "U4") (pin "P$36") (pinfunction "FLASH_CS_P$36") (pintype "bidirectional"))
    )
    (net (code "121") (name "unconnected-(U4-I2C0{slash}~{SPI0}-PadP$53)") (class "Default")
      (node (ref "U4") (pin "P$53") (pinfunction "I2C0/~{SPI0}_P$53") (pintype "bidirectional"))
    )
    (net (code "122") (name "unconnected-(U4-MISO0-PadP$57)") (class "Default")
      (node (ref "U4") (pin "P$57") (pinfunction "MISO0_P$57") (pintype "bidirectional"))
    )
    (net (code "123") (name "unconnected-(U4-MOSI0{slash}SDA-PadP$56)") (class "Default")
      (node (ref "U4") (pin "P$56") (pinfunction "MOSI0/SDA_P$56") (pintype "bidirectional"))
    )
    (net (code "124") (name "unconnected-(U4-ONEWIRE-PadP$54)") (class "Default")
      (node (ref "U4") (pin "P$54") (pinfunction "ONEWIRE_P$54") (pintype "bidirectional"))
    )
    (net (code "125") (name "unconnected-(U4-P2.1-PadP$39)") (class "Default")
      (node (ref "U4") (pin "P$39") (pinfunction "P2.1_P$39") (pintype "bidirectional"))
    )
    (net (code "126") (name "unconnected-(U4-P2.3-PadP$40)") (class "Default")
      (node (ref "U4") (pin "P$40") (pinfunction "P2.3_P$40") (pintype "bidirectional"))
    )
    (net (code "127") (name "unconnected-(U4-P2.6-PadP$41)") (class "Default")
      (node (ref "U4") (pin "P$41") (pinfunction "P2.6_P$41") (pintype "bidirectional"))
    )
    (net (code "128") (name "unconnected-(U4-P5.0-PadP$2)") (class "Default")
      (node (ref "U4") (pin "P$2") (pinfunction "P5.0_P$2") (pintype "bidirectional"))
    )
    (net (code "129") (name "unconnected-(U4-P5.1-PadP$3)") (class "Default")
      (node (ref "U4") (pin "P$3") (pinfunction "P5.1_P$3") (pintype "bidirectional"))
    )
    (net (code "130") (name "unconnected-(U4-P5.2-PadP$4)") (class "Default")
      (node (ref "U4") (pin "P$4") (pinfunction "P5.2_P$4") (pintype "bidirectional"))
    )
    (net (code "131") (name "unconnected-(U4-P5.7-PadP$9)") (class "Default")
      (node (ref "U4") (pin "P$9") (pinfunction "P5.7_P$9") (pintype "bidirectional"))
    )
    (net (code "132") (name "unconnected-(U4-RADIO_CCA-PadP$49)") (class "Default")
      (node (ref "U4") (pin "P$49") (pinfunction "RADIO_CCA_P$49") (pintype "bidirectional"))
    )
    (net (code "133") (name "unconnected-(U4-RADIO_CS-PadP$48)") (class "Default")
      (node (ref "U4") (pin "P$48") (pinfunction "RADIO_CS_P$48") (pintype "bidirectional"))
    )
    (net (code "134") (name "unconnected-(U4-RADIO_SFD-PadP$50)") (class "Default")
      (node (ref "U4") (pin "P$50") (pinfunction "RADIO_SFD_P$50") (pintype "bidirectional"))
    )
    (net (code "135") (name "unconnected-(U4-RFTXRX-PadP$45)") (class "Default")
      (node (ref "U4") (pin "P$45") (pinfunction "RFTXRX_P$45") (pintype "bidirectional"))
    )
    (net (code "136") (name "unconnected-(U4-SCLK0{slash}SCL-PadP$58)") (class "Default")
      (node (ref "U4") (pin "P$58") (pinfunction "SCLK0/SCL_P$58") (pintype "bidirectional"))
    )
    (net (code "137") (name "unconnected-(U4-STE0-PadP$55)") (class "Default")
      (node (ref "U4") (pin "P$55") (pinfunction "STE0_P$55") (pintype "bidirectional"))
    )
    (net (code "138") (name "unconnected-(U4-UART0RX-PadP$60)") (class "Default")
      (node (ref "U4") (pin "P$60") (pinfunction "UART0RX_P$60") (pintype "bidirectional"))
    )
    (net (code "139") (name "unconnected-(U4-UART0TX-PadP$59)") (class "Default")
      (node (ref "U4") (pin "P$59") (pinfunction "UART0TX_P$59") (pintype "bidirectional"))
    )
    (net (code "140") (name "unconnected-(U4-VEREF+-PadP$28)") (class "Default")
      (node (ref "U4") (pin "P$28") (pinfunction "VEREF+_P$28") (pintype "bidirectional"))
    )
    (net (code "141") (name "unconnected-(U4-VEREF--PadP$29)") (class "Default")
      (node (ref "U4") (pin "P$29") (pinfunction "VEREF-_P$29") (pintype "bidirectional"))
    )
    (net (code "142") (name "unconnected-(U4-VREF+-PadP$27)") (class "Default")
      (node (ref "U4") (pin "P$27") (pinfunction "VREF+_P$27") (pintype "bidirectional"))
    )
    (net (code "143") (name "unconnected-(U4-XOSC16IN-PadP$64)") (class "Default")
      (node (ref "U4") (pin "P$64") (pinfunction "XOSC16IN_P$64") (pintype "bidirectional"))
    )
    (net (code "144") (name "unconnected-(U4-XOSC16OUT-PadP$63)") (class "Default")
      (node (ref "U4") (pin "P$63") (pinfunction "XOSC16OUT_P$63") (pintype "bidirectional"))
    )
    (net (code "145") (name "unconnected-(U4-XT2IN-PadP$11)") (class "Default")
      (node (ref "U4") (pin "P$11") (pinfunction "XT2IN_P$11") (pintype "bidirectional"))
    )
    (net (code "146") (name "unconnected-(U4-XT2OUT-PadP$10)") (class "Default")
      (node (ref "U4") (pin "P$10") (pinfunction "XT2OUT_P$10") (pintype "bidirectional"))
    )
  )
)
